# SensWear_Memory.net
KiCad netlist of a schematic drawn in Altium Designer
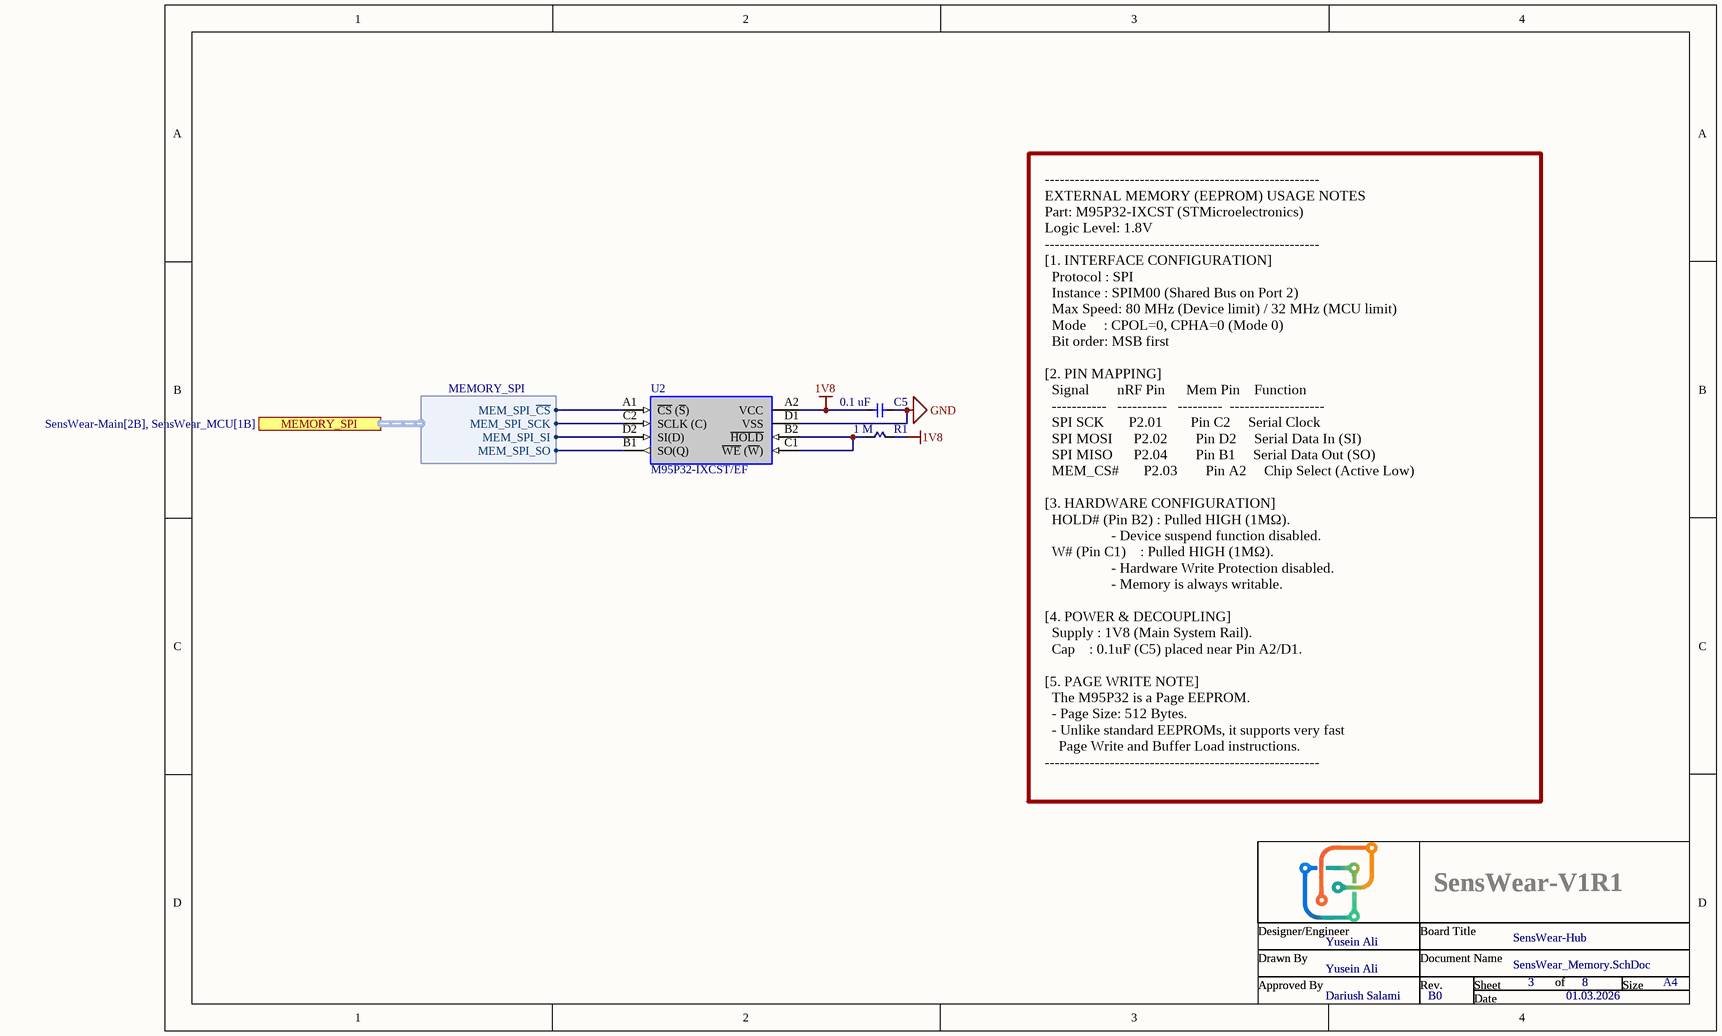
[diagram p0: SensWear_Memory.SchDoc]

(export (version "E")
  (design (tool "Eeschema 10.0.6"))
  (components
    (comp (ref "C5")
      (value "0.1 uF")
      (footprint "CAPC1005X05N")
      (description "CAP CER 0.1UF 16V X5R 0402")
      (fields
        (field (name "MANUFACTURER") "Murata Electronics")
        (field (name "MANUFACTURER PART NUMBER") "GRM155R61C104KA88D")
      )
      (libsource (lib "SensWearComponents") (part "GRM155R61C104KA88D__2"))
    )
    (comp (ref "R1")
      (value "1 M")
      (footprint "RESC1005X04N")
      (description "RES SMD 1M OHM 1% 1/10W 0402")
      (fields
        (field (name "MANUFACTURER") "Panasonic Electronic Components")
        (field (name "MANUFACTURER PART NUMBER") "ERJ-2RKF1004X")
      )
      (libsource (lib "SensWearComponents") (part "ERJ-2RKF1004X"))
    )
    (comp (ref "U2")
      (value "M95P32-IXCST/EF")
      (footprint "BGA8C70P2X4_153X261X58")
      (description "M95P32-I Series 32 Mb (4 M x 8) 80 MHz SPI EEPROM Memory IC - WLCSP-8")
      (fields (field (name "MANUFACTURER") "STMicroelectronics"))
      (libsource (lib "SensWearComponents") (part "M95P32-IXCST/EF"))
    )
  )
  (nets
    (net (code "2") (name "/MEM_SPI_SCK") (class "Default")
      (node (ref "U2") (pin "C2") (pinfunction "SCLK_(C)_C2") (pintype "input"))
    )
    (net (code "3") (name "/MEM_SPI_SI") (class "Default")
      (node (ref "U2") (pin "D2") (pinfunction "SI(D)_D2") (pintype "input"))
    )
    (net (code "4") (name "/MEM_SPI_SO") (class "Default")
      (node (ref "U2") (pin "B1") (pinfunction "SO(Q)_B1") (pintype "output"))
    )
    (net (code "5") (name "/MEM_SPI_~{CS}") (class "Default")
      (node (ref "U2") (pin "A1") (pinfunction "~{CS}_(~{S})_A1") (pintype "input"))
    )
    (net (code "7") (name "1V8") (class "Default")
      (node (ref "C5") (pin "2") (pinfunction "2_2") (pintype "passive"))
      (node (ref "R1") (pin "2") (pinfunction "2_2") (pintype "passive"))
      (node (ref "U2") (pin "A2") (pinfunction "VCC_A2") (pintype "power_in"))
    )
    (net (code "8") (name "GND") (class "Default")
      (node (ref "C5") (pin "1") (pinfunction "1_1") (pintype "passive"))
      (node (ref "U2") (pin "D1") (pinfunction "VSS_D1") (pintype "power_in"))
    )
    (net (code "9") (name "Net-(U2-~{HOLD})") (class "Default")
      (node (ref "R1") (pin "1") (pinfunction "1_1") (pintype "passive"))
      (node (ref "U2") (pin "B2") (pinfunction "~{HOLD}_B2") (pintype "input"))
      (node (ref "U2") (pin "C1") (pinfunction "~{WE}_(~{W})_C1") (pintype "input"))
    )
  )
)
